# Quadrature_Mixers_FIXED_WITH_BIASING.net
KiCad netlist of a schematic drawn in Altium Designer
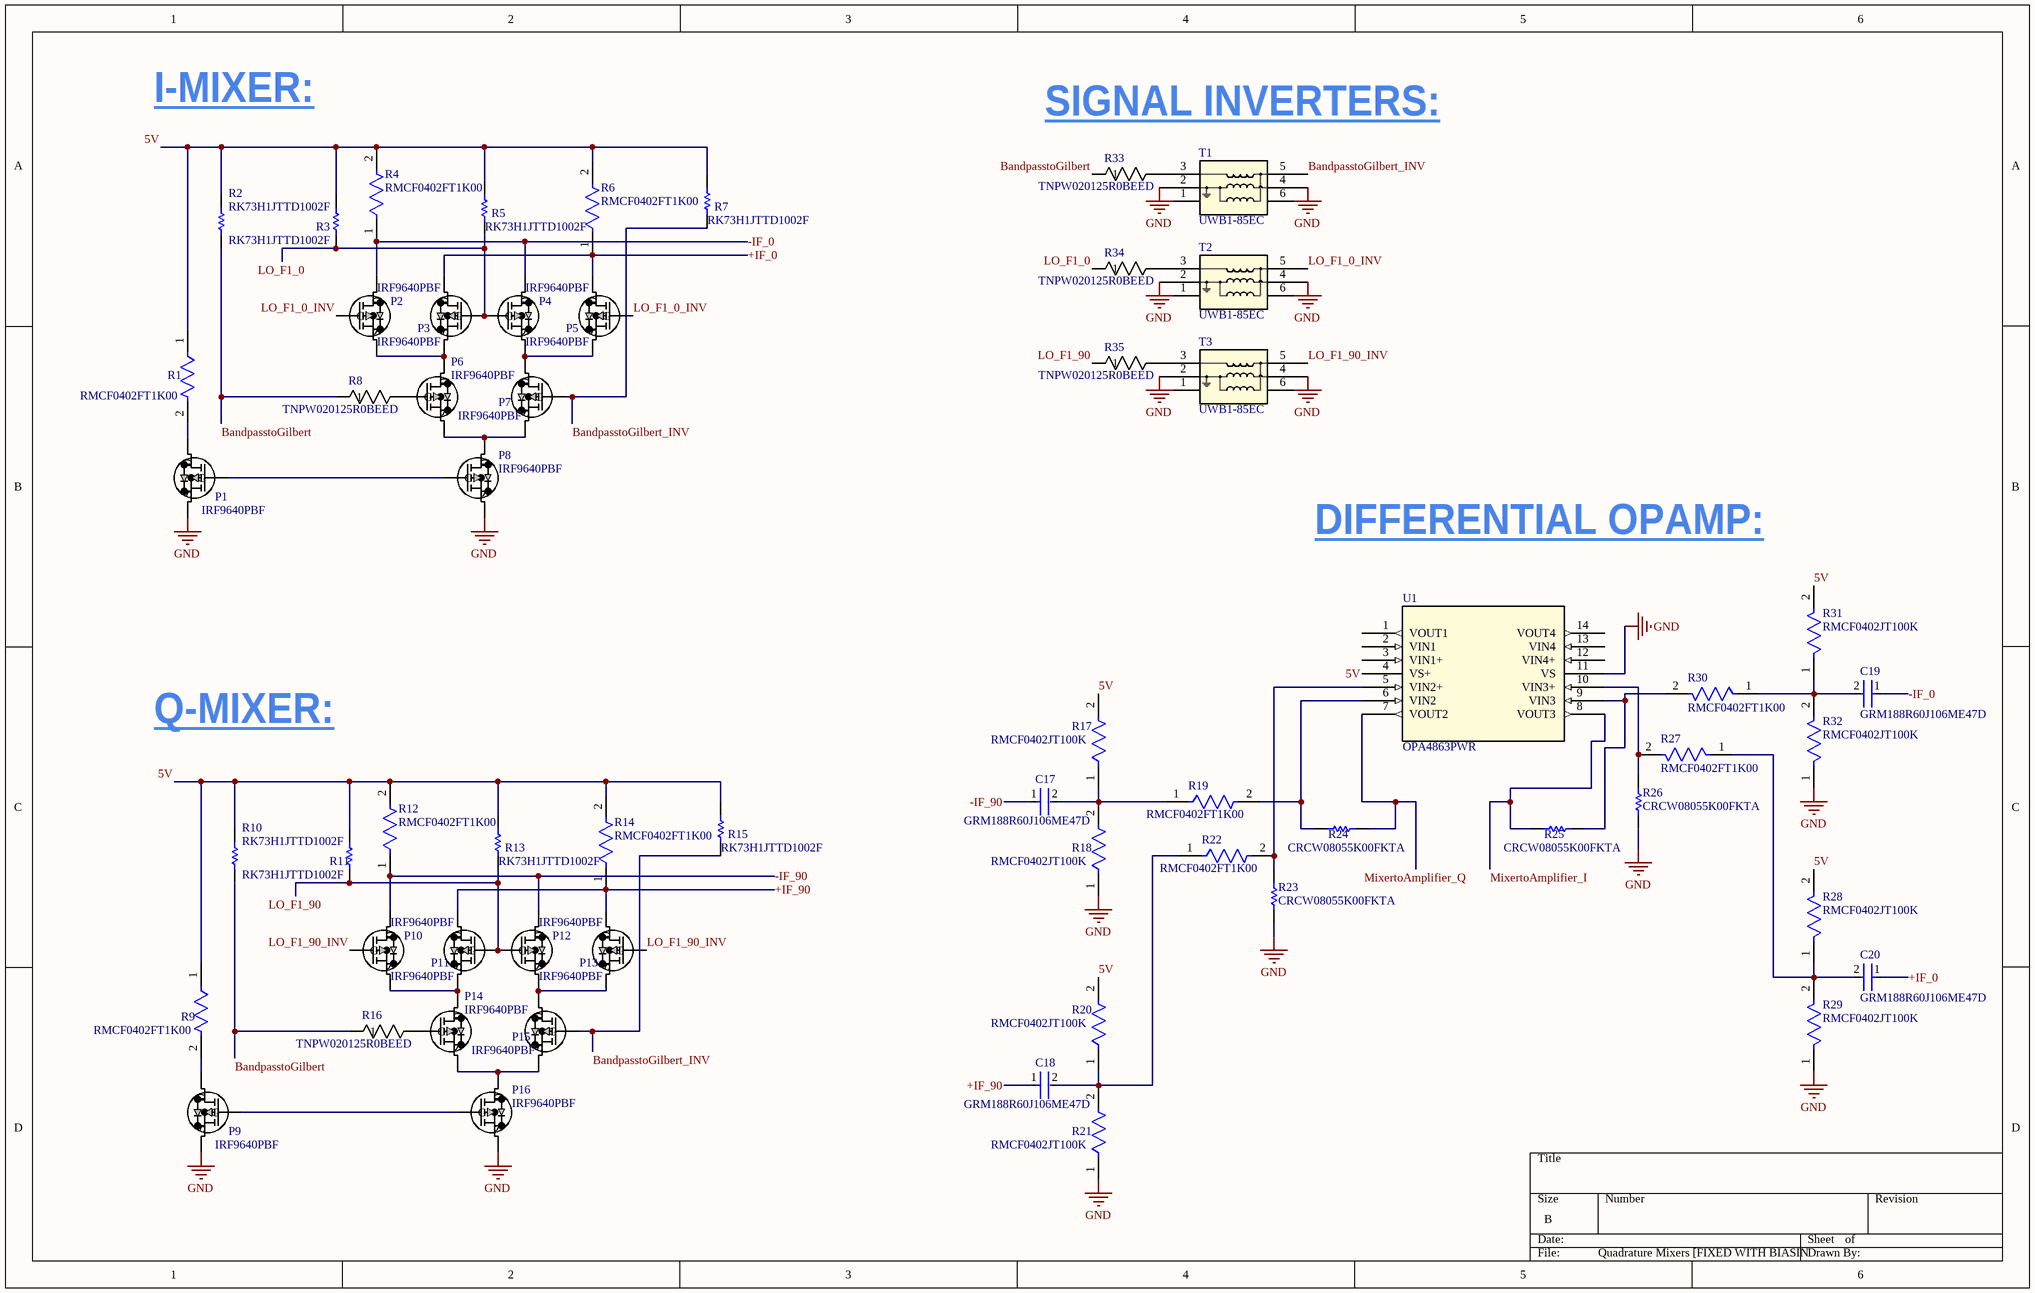
[diagram p0: Quadrature Mixers [FIXED WITH BIASING].SchDoc]

(export (version "E")
  (design (tool "Eeschema 10.0.6"))
  (components
    (comp (ref "C17")
      (value "GRM188R60J106ME47D")
      (footprint "FP-GRM188-0_1-e0_2_0_55-IPC_A")
      (description "Chip Multilayer Ceramic Capacitors for General Purpose, 0603, 10uF, X5R, 15%, 20%, 6.3V")
      (fields (field (name "VOLTAGE") "6.3V") (field (name "TOLERANCE") "20%"))
      (libsource (lib "Altium Content Vault") (part "02cd4be3c70576c341d710602a673aa"))
    )
    (comp (ref "C18")
      (value "GRM188R60J106ME47D")
      (footprint "FP-GRM188-0_1-e0_2_0_55-IPC_A")
      (description "Chip Multilayer Ceramic Capacitors for General Purpose, 0603, 10uF, X5R, 15%, 20%, 6.3V")
      (fields (field (name "VOLTAGE") "6.3V") (field (name "TOLERANCE") "20%"))
      (libsource (lib "Altium Content Vault") (part "02cd4be3c70576c341d710602a673aa"))
    )
    (comp (ref "C19")
      (value "GRM188R60J106ME47D")
      (footprint "FP-GRM188-0_1-e0_2_0_55-IPC_A")
      (description "Chip Multilayer Ceramic Capacitors for General Purpose, 0603, 10uF, X5R, 15%, 20%, 6.3V")
      (fields (field (name "VOLTAGE") "6.3V") (field (name "TOLERANCE") "20%"))
      (libsource (lib "Altium Content Vault") (part "02cd4be3c70576c341d710602a673aa"))
    )
    (comp (ref "C20")
      (value "GRM188R60J106ME47D")
      (footprint "FP-GRM188-0_1-e0_2_0_55-IPC_A")
      (description "Chip Multilayer Ceramic Capacitors for General Purpose, 0603, 10uF, X5R, 15%, 20%, 6.3V")
      (fields (field (name "VOLTAGE") "6.3V") (field (name "TOLERANCE") "20%"))
      (libsource (lib "Altium Content Vault") (part "02cd4be3c70576c341d710602a673aa"))
    )
    (comp (ref "P1")
      (value "IRF9640PBF")
      (footprint "TO220AB_VIS")
      (description "No Description Available")
      (libsource (lib "IRF9640PBF") (part "IRF9640PBF"))
    )
    (comp (ref "P2")
      (value "IRF9640PBF")
      (footprint "TO220AB_VIS")
      (description "No Description Available")
      (libsource (lib "IRF9640PBF") (part "IRF9640PBF"))
    )
    (comp (ref "P3")
      (value "IRF9640PBF")
      (footprint "TO220AB_VIS")
      (description "No Description Available")
      (libsource (lib "IRF9640PBF") (part "IRF9640PBF"))
    )
    (comp (ref "P4")
      (value "IRF9640PBF")
      (footprint "TO220AB_VIS")
      (description "No Description Available")
      (libsource (lib "IRF9640PBF") (part "IRF9640PBF"))
    )
    (comp (ref "P5")
      (value "IRF9640PBF")
      (footprint "TO220AB_VIS")
      (description "No Description Available")
      (libsource (lib "IRF9640PBF") (part "IRF9640PBF"))
    )
    (comp (ref "P6")
      (value "IRF9640PBF")
      (footprint "TO220AB_VIS")
      (description "No Description Available")
      (libsource (lib "IRF9640PBF") (part "IRF9640PBF"))
    )
    (comp (ref "P7")
      (value "IRF9640PBF")
      (footprint "TO220AB_VIS")
      (description "No Description Available")
      (libsource (lib "IRF9640PBF") (part "IRF9640PBF"))
    )
    (comp (ref "P8")
      (value "IRF9640PBF")
      (footprint "TO220AB_VIS")
      (description "No Description Available")
      (libsource (lib "IRF9640PBF") (part "IRF9640PBF"))
    )
    (comp (ref "P9")
      (value "IRF9640PBF")
      (footprint "TO220AB_VIS")
      (description "No Description Available")
      (libsource (lib "IRF9640PBF") (part "IRF9640PBF"))
    )
    (comp (ref "P10")
      (value "IRF9640PBF")
      (footprint "TO220AB_VIS")
      (description "No Description Available")
      (libsource (lib "IRF9640PBF") (part "IRF9640PBF"))
    )
    (comp (ref "P11")
      (value "IRF9640PBF")
      (footprint "TO220AB_VIS")
      (description "No Description Available")
      (libsource (lib "IRF9640PBF") (part "IRF9640PBF"))
    )
    (comp (ref "P12")
      (value "IRF9640PBF")
      (footprint "TO220AB_VIS")
      (description "No Description Available")
      (libsource (lib "IRF9640PBF") (part "IRF9640PBF"))
    )
    (comp (ref "P13")
      (value "IRF9640PBF")
      (footprint "TO220AB_VIS")
      (description "No Description Available")
      (libsource (lib "IRF9640PBF") (part "IRF9640PBF"))
    )
    (comp (ref "P14")
      (value "IRF9640PBF")
      (footprint "TO220AB_VIS")
      (description "No Description Available")
      (libsource (lib "IRF9640PBF") (part "IRF9640PBF"))
    )
    (comp (ref "P15")
      (value "IRF9640PBF")
      (footprint "TO220AB_VIS")
      (description "No Description Available")
      (libsource (lib "IRF9640PBF") (part "IRF9640PBF"))
    )
    (comp (ref "P16")
      (value "IRF9640PBF")
      (footprint "TO220AB_VIS")
      (description "No Description Available")
      (libsource (lib "IRF9640PBF") (part "IRF9640PBF"))
    )
    (comp (ref "R1")
      (value "RMCF0402FT1K00")
      (footprint "FP-RMCF0402-MFG")
      (description "1kΩ ±1% 0.063W 0402 Thick Film Chip Resistor AEC-Q200 compliant")
      (fields (field (name "TOLERANCE") "1%"))
      (libsource (lib "Altium Content Vault") (part "1029c3af85768c4190bb7ad29bc67b5"))
    )
    (comp (ref "R2")
      (value "RK73H1JTTD1002F")
      (footprint "RESC1608X55X30ML20T10")
      (fields (field (name "MANUFACTURER") "KOA Speer"))
      (libsource (lib "Altium Content Vault") (part "RES"))
    )
    (comp (ref "R3")
      (value "RK73H1JTTD1002F")
      (footprint "RESC1608X55X30ML20T10")
      (fields (field (name "MANUFACTURER") "KOA Speer"))
      (libsource (lib "Altium Content Vault") (part "RES"))
    )
    (comp (ref "R4")
      (value "RMCF0402FT1K00")
      (footprint "FP-RMCF0402-MFG")
      (description "1kΩ ±1% 0.063W 0402 Thick Film Chip Resistor AEC-Q200 compliant")
      (fields (field (name "TOLERANCE") "1%"))
      (libsource (lib "Altium Content Vault") (part "1029c3af85768c4190bb7ad29bc67b5"))
    )
    (comp (ref "R5")
      (value "RK73H1JTTD1002F")
      (footprint "RESC1608X55X30ML20T10")
      (fields (field (name "MANUFACTURER") "KOA Speer"))
      (libsource (lib "Altium Content Vault") (part "RES"))
    )
    (comp (ref "R6")
      (value "RMCF0402FT1K00")
      (footprint "FP-RMCF0402-MFG")
      (description "1kΩ ±1% 0.063W 0402 Thick Film Chip Resistor AEC-Q200 compliant")
      (fields (field (name "TOLERANCE") "1%"))
      (libsource (lib "Altium Content Vault") (part "1029c3af85768c4190bb7ad29bc67b5"))
    )
    (comp (ref "R7")
      (value "RK73H1JTTD1002F")
      (footprint "RESC1608X55X30ML20T10")
      (fields (field (name "MANUFACTURER") "KOA Speer"))
      (libsource (lib "Altium Content Vault") (part "RES"))
    )
    (comp (ref "R8")
      (value "TNPW020125R0BEED")
      (footprint "RES_TNPW0201_VIS")
      (description "RES 25 OHM 0.1% 0.075W 0201")
      (libsource (lib "TNPW020125R0BEED") (part "TNPW020125R0BEED"))
    )
    (comp (ref "R9")
      (value "RMCF0402FT1K00")
      (footprint "FP-RMCF0402-MFG")
      (description "1kΩ ±1% 0.063W 0402 Thick Film Chip Resistor AEC-Q200 compliant")
      (fields (field (name "TOLERANCE") "1%"))
      (libsource (lib "Altium Content Vault") (part "1029c3af85768c4190bb7ad29bc67b5"))
    )
    (comp (ref "R10")
      (value "RK73H1JTTD1002F")
      (footprint "RESC1608X55X30ML20T10")
      (fields (field (name "MANUFACTURER") "KOA Speer"))
      (libsource (lib "Altium Content Vault") (part "RES"))
    )
    (comp (ref "R11")
      (value "RK73H1JTTD1002F")
      (footprint "RESC1608X55X30ML20T10")
      (fields (field (name "MANUFACTURER") "KOA Speer"))
      (libsource (lib "Altium Content Vault") (part "RES"))
    )
    (comp (ref "R12")
      (value "RMCF0402FT1K00")
      (footprint "FP-RMCF0402-MFG")
      (description "1kΩ ±1% 0.063W 0402 Thick Film Chip Resistor AEC-Q200 compliant")
      (fields (field (name "TOLERANCE") "1%"))
      (libsource (lib "Altium Content Vault") (part "1029c3af85768c4190bb7ad29bc67b5"))
    )
    (comp (ref "R13")
      (value "RK73H1JTTD1002F")
      (footprint "RESC1608X55X30ML20T10")
      (fields (field (name "MANUFACTURER") "KOA Speer"))
      (libsource (lib "Altium Content Vault") (part "RES"))
    )
    (comp (ref "R14")
      (value "RMCF0402FT1K00")
      (footprint "FP-RMCF0402-MFG")
      (description "1kΩ ±1% 0.063W 0402 Thick Film Chip Resistor AEC-Q200 compliant")
      (fields (field (name "TOLERANCE") "1%"))
      (libsource (lib "Altium Content Vault") (part "1029c3af85768c4190bb7ad29bc67b5"))
    )
    (comp (ref "R15")
      (value "RK73H1JTTD1002F")
      (footprint "RESC1608X55X30ML20T10")
      (fields (field (name "MANUFACTURER") "KOA Speer"))
      (libsource (lib "Altium Content Vault") (part "RES"))
    )
    (comp (ref "R16")
      (value "TNPW020125R0BEED")
      (footprint "RES_TNPW0201_VIS")
      (description "RES 25 OHM 0.1% 0.075W 0201")
      (libsource (lib "TNPW020125R0BEED") (part "TNPW020125R0BEED"))
    )
    (comp (ref "R17")
      (value "RMCF0402JT100K")
      (footprint "FP-RMCF0402-MFG")
      (description "100kΩ ±5% 0.063W 0402 Thick Film Chip Resistor AEC-Q200 compliant")
      (fields (field (name "TOLERANCE") "5%"))
      (libsource (lib "Altium Content Vault") (part "1029c3af85768c4190bb7ad29bc67b5"))
    )
    (comp (ref "R18")
      (value "RMCF0402JT100K")
      (footprint "FP-RMCF0402-MFG")
      (description "100kΩ ±5% 0.063W 0402 Thick Film Chip Resistor AEC-Q200 compliant")
      (fields (field (name "TOLERANCE") "5%"))
      (libsource (lib "Altium Content Vault") (part "1029c3af85768c4190bb7ad29bc67b5"))
    )
    (comp (ref "R19")
      (value "RMCF0402FT1K00")
      (footprint "FP-RMCF0402-MFG")
      (description "1kΩ ±1% 0.063W 0402 Thick Film Chip Resistor AEC-Q200 compliant")
      (fields (field (name "TOLERANCE") "1%"))
      (libsource (lib "Altium Content Vault") (part "1029c3af85768c4190bb7ad29bc67b5"))
    )
    (comp (ref "R20")
      (value "RMCF0402JT100K")
      (footprint "FP-RMCF0402-MFG")
      (description "100kΩ ±5% 0.063W 0402 Thick Film Chip Resistor AEC-Q200 compliant")
      (fields (field (name "TOLERANCE") "5%"))
      (libsource (lib "Altium Content Vault") (part "1029c3af85768c4190bb7ad29bc67b5"))
    )
    (comp (ref "R21")
      (value "RMCF0402JT100K")
      (footprint "FP-RMCF0402-MFG")
      (description "100kΩ ±5% 0.063W 0402 Thick Film Chip Resistor AEC-Q200 compliant")
      (fields (field (name "TOLERANCE") "5%"))
      (libsource (lib "Altium Content Vault") (part "1029c3af85768c4190bb7ad29bc67b5"))
    )
    (comp (ref "R22")
      (value "RMCF0402FT1K00")
      (footprint "FP-RMCF0402-MFG")
      (description "1kΩ ±1% 0.063W 0402 Thick Film Chip Resistor AEC-Q200 compliant")
      (fields (field (name "TOLERANCE") "1%"))
      (libsource (lib "Altium Content Vault") (part "1029c3af85768c4190bb7ad29bc67b5"))
    )
    (comp (ref "R23")
      (value "CRCW08055K00FKTA")
      (footprint "RESC2013X50X30ML20T20")
      (fields (field (name "MANUFACTURER") "Vishay Dale"))
      (libsource (lib "Altium Content Vault") (part "RES"))
    )
    (comp (ref "R24")
      (value "CRCW08055K00FKTA")
      (footprint "RESC2013X50X30ML20T20")
      (fields (field (name "MANUFACTURER") "Vishay Dale"))
      (libsource (lib "Altium Content Vault") (part "RES"))
    )
    (comp (ref "R25")
      (value "CRCW08055K00FKTA")
      (footprint "RESC2013X50X30ML20T20")
      (fields (field (name "MANUFACTURER") "Vishay Dale"))
      (libsource (lib "Altium Content Vault") (part "RES"))
    )
    (comp (ref "R26")
      (value "CRCW08055K00FKTA")
      (footprint "RESC2013X50X30ML20T20")
      (fields (field (name "MANUFACTURER") "Vishay Dale"))
      (libsource (lib "Altium Content Vault") (part "RES"))
    )
    (comp (ref "R27")
      (value "RMCF0402FT1K00")
      (footprint "FP-RMCF0402-MFG")
      (description "1kΩ ±1% 0.063W 0402 Thick Film Chip Resistor AEC-Q200 compliant")
      (fields (field (name "TOLERANCE") "1%"))
      (libsource (lib "Altium Content Vault") (part "1029c3af85768c4190bb7ad29bc67b5"))
    )
    (comp (ref "R28")
      (value "RMCF0402JT100K")
      (footprint "FP-RMCF0402-MFG")
      (description "100kΩ ±5% 0.063W 0402 Thick Film Chip Resistor AEC-Q200 compliant")
      (fields (field (name "TOLERANCE") "5%"))
      (libsource (lib "Altium Content Vault") (part "1029c3af85768c4190bb7ad29bc67b5"))
    )
    (comp (ref "R29")
      (value "RMCF0402JT100K")
      (footprint "FP-RMCF0402-MFG")
      (description "100kΩ ±5% 0.063W 0402 Thick Film Chip Resistor AEC-Q200 compliant")
      (fields (field (name "TOLERANCE") "5%"))
      (libsource (lib "Altium Content Vault") (part "1029c3af85768c4190bb7ad29bc67b5"))
    )
    (comp (ref "R30")
      (value "RMCF0402FT1K00")
      (footprint "FP-RMCF0402-MFG")
      (description "1kΩ ±1% 0.063W 0402 Thick Film Chip Resistor AEC-Q200 compliant")
      (fields (field (name "TOLERANCE") "1%"))
      (libsource (lib "Altium Content Vault") (part "1029c3af85768c4190bb7ad29bc67b5"))
    )
    (comp (ref "R31")
      (value "RMCF0402JT100K")
      (footprint "FP-RMCF0402-MFG")
      (description "100kΩ ±5% 0.063W 0402 Thick Film Chip Resistor AEC-Q200 compliant")
      (fields (field (name "TOLERANCE") "5%"))
      (libsource (lib "Altium Content Vault") (part "1029c3af85768c4190bb7ad29bc67b5"))
    )
    (comp (ref "R32")
      (value "RMCF0402JT100K")
      (footprint "FP-RMCF0402-MFG")
      (description "100kΩ ±5% 0.063W 0402 Thick Film Chip Resistor AEC-Q200 compliant")
      (fields (field (name "TOLERANCE") "5%"))
      (libsource (lib "Altium Content Vault") (part "1029c3af85768c4190bb7ad29bc67b5"))
    )
    (comp (ref "R33")
      (value "TNPW020125R0BEED")
      (footprint "RES_TNPW0201_VIS")
      (description "RES 25 OHM 0.1% 0.075W 0201")
      (libsource (lib "TNPW020125R0BEED") (part "TNPW020125R0BEED"))
    )
    (comp (ref "R34")
      (value "TNPW020125R0BEED")
      (footprint "RES_TNPW0201_VIS")
      (description "RES 25 OHM 0.1% 0.075W 0201")
      (libsource (lib "TNPW020125R0BEED") (part "TNPW020125R0BEED"))
    )
    (comp (ref "R35")
      (value "TNPW020125R0BEED")
      (footprint "RES_TNPW0201_VIS")
      (description "RES 25 OHM 0.1% 0.075W 0201")
      (libsource (lib "TNPW020125R0BEED") (part "TNPW020125R0BEED"))
    )
    (comp (ref "T1")
      (value "UWB1-85EC")
      (footprint "UWB1UWB2_COC")
      (libsource (lib "UWB1-85EC") (part "UWB1-85EC"))
    )
    (comp (ref "T2")
      (value "UWB1-85EC")
      (footprint "UWB1UWB2_COC")
      (libsource (lib "UWB1-85EC") (part "UWB1-85EC"))
    )
    (comp (ref "T3")
      (value "UWB1-85EC")
      (footprint "UWB1UWB2_COC")
      (libsource (lib "UWB1-85EC") (part "UWB1-85EC"))
    )
    (comp (ref "U1")
      (value "OPA4863PWR")
      (footprint "PW14_TEX")
      (description "No Description Available")
      (libsource (lib "OPA4863PWR") (part "OPA4863PWR"))
    )
  )
  (nets
    (net (code "1") (name "/+IF_0") (class "Default")
      (node (ref "C20") (pin "1") (pinfunction "1_1") (pintype "passive"))
      (node (ref "P3") (pin "2") (pinfunction "D_2") (pintype "passive"))
      (node (ref "P5") (pin "2") (pinfunction "D_2") (pintype "passive"))
      (node (ref "R6") (pin "1") (pinfunction "1_1") (pintype "passive"))
    )
    (net (code "2") (name "/+IF_90") (class "Default")
      (node (ref "C18") (pin "1") (pinfunction "1_1") (pintype "passive"))
      (node (ref "P11") (pin "2") (pinfunction "D_2") (pintype "passive"))
      (node (ref "P13") (pin "2") (pinfunction "D_2") (pintype "passive"))
      (node (ref "R14") (pin "1") (pinfunction "1_1") (pintype "passive"))
    )
    (net (code "3") (name "/-IF_0") (class "Default")
      (node (ref "C19") (pin "1") (pinfunction "1_1") (pintype "passive"))
      (node (ref "P2") (pin "2") (pinfunction "D_2") (pintype "passive"))
      (node (ref "P4") (pin "2") (pinfunction "D_2") (pintype "passive"))
      (node (ref "R4") (pin "1") (pinfunction "1_1") (pintype "passive"))
    )
    (net (code "4") (name "/-IF_90") (class "Default")
      (node (ref "C17") (pin "1") (pinfunction "1_1") (pintype "passive"))
      (node (ref "P10") (pin "2") (pinfunction "D_2") (pintype "passive"))
      (node (ref "P12") (pin "2") (pinfunction "D_2") (pintype "passive"))
      (node (ref "R12") (pin "1") (pinfunction "1_1") (pintype "passive"))
    )
    (net (code "5") (name "/5V") (class "Default")
      (node (ref "R1") (pin "1") (pinfunction "1_1") (pintype "passive"))
      (node (ref "R10") (pin "2") (pinfunction "2_2") (pintype "passive"))
      (node (ref "R11") (pin "2") (pinfunction "2_2") (pintype "passive"))
      (node (ref "R12") (pin "2") (pinfunction "2_2") (pintype "passive"))
      (node (ref "R13") (pin "2") (pinfunction "2_2") (pintype "passive"))
      (node (ref "R14") (pin "2") (pinfunction "2_2") (pintype "passive"))
      (node (ref "R15") (pin "2") (pinfunction "2_2") (pintype "passive"))
      (node (ref "R17") (pin "2") (pinfunction "2_2") (pintype "passive"))
      (node (ref "R2") (pin "2") (pinfunction "2_2") (pintype "passive"))
      (node (ref "R20") (pin "2") (pinfunction "2_2") (pintype "passive"))
      (node (ref "R28") (pin "2") (pinfunction "2_2") (pintype "passive"))
      (node (ref "R3") (pin "2") (pinfunction "2_2") (pintype "passive"))
      (node (ref "R31") (pin "2") (pinfunction "2_2") (pintype "passive"))
      (node (ref "R4") (pin "2") (pinfunction "2_2") (pintype "passive"))
      (node (ref "R5") (pin "2") (pinfunction "2_2") (pintype "passive"))
      (node (ref "R6") (pin "2") (pinfunction "2_2") (pintype "passive"))
      (node (ref "R7") (pin "2") (pinfunction "2_2") (pintype "passive"))
      (node (ref "R9") (pin "1") (pinfunction "1_1") (pintype "passive"))
      (node (ref "U1") (pin "4") (pinfunction "VS+_4") (pintype "power_in"))
    )
    (net (code "6") (name "/BandpasstoGilbert") (class "Default")
      (node (ref "R10") (pin "1") (pinfunction "1_1") (pintype "passive"))
      (node (ref "R16") (pin "1") (pinfunction "1_1") (pintype "passive"))
      (node (ref "R2") (pin "1") (pinfunction "1_1") (pintype "passive"))
      (node (ref "R33") (pin "1") (pinfunction "1_1") (pintype "passive"))
      (node (ref "R8") (pin "1") (pinfunction "1_1") (pintype "passive"))
    )
    (net (code "7") (name "/BandpasstoGilbert_INV") (class "Default")
      (node (ref "P15") (pin "1") (pinfunction "G_1") (pintype "passive"))
      (node (ref "P7") (pin "1") (pinfunction "G_1") (pintype "passive"))
      (node (ref "R15") (pin "1") (pinfunction "1_1") (pintype "passive"))
      (node (ref "R7") (pin "1") (pinfunction "1_1") (pintype "passive"))
      (node (ref "T1") (pin "5") (pinfunction "5_5") (pintype "passive"))
    )
    (net (code "8") (name "/LO_F1_0") (class "Default")
      (node (ref "P3") (pin "1") (pinfunction "G_1") (pintype "passive"))
      (node (ref "P4") (pin "1") (pinfunction "G_1") (pintype "passive"))
      (node (ref "R3") (pin "1") (pinfunction "1_1") (pintype "passive"))
      (node (ref "R34") (pin "1") (pinfunction "1_1") (pintype "passive"))
      (node (ref "R5") (pin "1") (pinfunction "1_1") (pintype "passive"))
    )
    (net (code "9") (name "/LO_F1_0_INV") (class "Default")
      (node (ref "P2") (pin "1") (pinfunction "G_1") (pintype "passive"))
      (node (ref "P5") (pin "1") (pinfunction "G_1") (pintype "passive"))
      (node (ref "T2") (pin "5") (pinfunction "5_5") (pintype "passive"))
    )
    (net (code "10") (name "/LO_F1_90") (class "Default")
      (node (ref "P11") (pin "1") (pinfunction "G_1") (pintype "passive"))
      (node (ref "P12") (pin "1") (pinfunction "G_1") (pintype "passive"))
      (node (ref "R11") (pin "1") (pinfunction "1_1") (pintype "passive"))
      (node (ref "R13") (pin "1") (pinfunction "1_1") (pintype "passive"))
      (node (ref "R35") (pin "1") (pinfunction "1_1") (pintype "passive"))
    )
    (net (code "11") (name "/LO_F1_90_INV") (class "Default")
      (node (ref "P10") (pin "1") (pinfunction "G_1") (pintype "passive"))
      (node (ref "P13") (pin "1") (pinfunction "G_1") (pintype "passive"))
      (node (ref "T3") (pin "5") (pinfunction "5_5") (pintype "passive"))
    )
    (net (code "12") (name "/MixertoAmplifier_I") (class "Default")
      (node (ref "R25") (pin "1") (pinfunction "1_1") (pintype "passive"))
      (node (ref "U1") (pin "8") (pinfunction "VOUT3_8") (pintype "output"))
    )
    (net (code "13") (name "/MixertoAmplifier_Q") (class "Default")
      (node (ref "R24") (pin "2") (pinfunction "2_2") (pintype "passive"))
      (node (ref "U1") (pin "7") (pinfunction "VOUT2_7") (pintype "output"))
    )
    (net (code "14") (name "GND") (class "Default")
      (node (ref "P1") (pin "3") (pinfunction "S_3") (pintype "passive"))
      (node (ref "P16") (pin "3") (pinfunction "S_3") (pintype "passive"))
      (node (ref "P8") (pin "3") (pinfunction "S_3") (pintype "passive"))
      (node (ref "P9") (pin "3") (pinfunction "S_3") (pintype "passive"))
      (node (ref "R18") (pin "1") (pinfunction "1_1") (pintype "passive"))
      (node (ref "R21") (pin "1") (pinfunction "1_1") (pintype "passive"))
      (node (ref "R23") (pin "1") (pinfunction "1_1") (pintype "passive"))
      (node (ref "R26") (pin "1") (pinfunction "1_1") (pintype "passive"))
      (node (ref "R29") (pin "1") (pinfunction "1_1") (pintype "passive"))
      (node (ref "R32") (pin "1") (pinfunction "1_1") (pintype "passive"))
      (node (ref "T1") (pin "2") (pinfunction "2_2") (pintype "passive"))
      (node (ref "T1") (pin "4") (pinfunction "4_4") (pintype "passive"))
      (node (ref "T2") (pin "2") (pinfunction "2_2") (pintype "passive"))
      (node (ref "T2") (pin "4") (pinfunction "4_4") (pintype "passive"))
      (node (ref "T3") (pin "2") (pinfunction "2_2") (pintype "passive"))
      (node (ref "T3") (pin "4") (pinfunction "4_4") (pintype "passive"))
      (node (ref "U1") (pin "11") (pinfunction "VS_11") (pintype "power_in"))
    )
    (net (code "15") (name "Net-(C17-Pad2)") (class "Default")
      (node (ref "C17") (pin "2") (pinfunction "2_2") (pintype "passive"))
      (node (ref "R17") (pin "1") (pinfunction "1_1") (pintype "passive"))
      (node (ref "R18") (pin "2") (pinfunction "2_2") (pintype "passive"))
      (node (ref "R19") (pin "1") (pinfunction "1_1") (pintype "passive"))
    )
    (net (code "16") (name "Net-(C18-Pad2)") (class "Default")
      (node (ref "C18") (pin "2") (pinfunction "2_2") (pintype "passive"))
      (node (ref "R20") (pin "1") (pinfunction "1_1") (pintype "passive"))
      (node (ref "R21") (pin "2") (pinfunction "2_2") (pintype "passive"))
      (node (ref "R22") (pin "1") (pinfunction "1_1") (pintype "passive"))
    )
    (net (code "17") (name "Net-(C19-Pad2)") (class "Default")
      (node (ref "C19") (pin "2") (pinfunction "2_2") (pintype "passive"))
      (node (ref "R30") (pin "1") (pinfunction "1_1") (pintype "passive"))
      (node (ref "R31") (pin "1") (pinfunction "1_1") (pintype "passive"))
      (node (ref "R32") (pin "2") (pinfunction "2_2") (pintype "passive"))
    )
    (net (code "18") (name "Net-(C20-Pad2)") (class "Default")
      (node (ref "C20") (pin "2") (pinfunction "2_2") (pintype "passive"))
      (node (ref "R27") (pin "1") (pinfunction "1_1") (pintype "passive"))
      (node (ref "R28") (pin "1") (pinfunction "1_1") (pintype "passive"))
      (node (ref "R29") (pin "2") (pinfunction "2_2") (pintype "passive"))
    )
    (net (code "19") (name "Net-(P1-D)") (class "Default")
      (node (ref "P1") (pin "2") (pinfunction "D_2") (pintype "passive"))
      (node (ref "R1") (pin "2") (pinfunction "2_2") (pintype "passive"))
    )
    (net (code "20") (name "Net-(P1-G)") (class "Default")
      (node (ref "P1") (pin "1") (pinfunction "G_1") (pintype "passive"))
      (node (ref "P8") (pin "1") (pinfunction "G_1") (pintype "passive"))
    )
    (net (code "21") (name "Net-(P2-S)") (class "Default")
      (node (ref "P2") (pin "3") (pinfunction "S_3") (pintype "passive"))
      (node (ref "P3") (pin "3") (pinfunction "S_3") (pintype "passive"))
      (node (ref "P6") (pin "2") (pinfunction "D_2") (pintype "passive"))
    )
    (net (code "22") (name "Net-(P4-S)") (class "Default")
      (node (ref "P4") (pin "3") (pinfunction "S_3") (pintype "passive"))
      (node (ref "P5") (pin "3") (pinfunction "S_3") (pintype "passive"))
      (node (ref "P7") (pin "2") (pinfunction "D_2") (pintype "passive"))
    )
    (net (code "23") (name "Net-(P6-G)") (class "Default")
      (node (ref "P6") (pin "1") (pinfunction "G_1") (pintype "passive"))
      (node (ref "R8") (pin "2") (pinfunction "2_2") (pintype "passive"))
    )
    (net (code "24") (name "Net-(P6-S)") (class "Default")
      (node (ref "P6") (pin "3") (pinfunction "S_3") (pintype "passive"))
      (node (ref "P7") (pin "3") (pinfunction "S_3") (pintype "passive"))
      (node (ref "P8") (pin "2") (pinfunction "D_2") (pintype "passive"))
    )
    (net (code "25") (name "Net-(P9-D)") (class "Default")
      (node (ref "P9") (pin "2") (pinfunction "D_2") (pintype "passive"))
      (node (ref "R9") (pin "2") (pinfunction "2_2") (pintype "passive"))
    )
    (net (code "26") (name "Net-(P10-S)") (class "Default")
      (node (ref "P10") (pin "3") (pinfunction "S_3") (pintype "passive"))
      (node (ref "P11") (pin "3") (pinfunction "S_3") (pintype "passive"))
      (node (ref "P14") (pin "2") (pinfunction "D_2") (pintype "passive"))
    )
    (net (code "27") (name "Net-(P12-S)") (class "Default")
      (node (ref "P12") (pin "3") (pinfunction "S_3") (pintype "passive"))
      (node (ref "P13") (pin "3") (pinfunction "S_3") (pintype "passive"))
      (node (ref "P15") (pin "2") (pinfunction "D_2") (pintype "passive"))
    )
    (net (code "28") (name "Net-(P14-G)") (class "Default")
      (node (ref "P14") (pin "1") (pinfunction "G_1") (pintype "passive"))
      (node (ref "R16") (pin "2") (pinfunction "2_2") (pintype "passive"))
    )
    (net (code "29") (name "Net-(P14-S)") (class "Default")
      (node (ref "P14") (pin "3") (pinfunction "S_3") (pintype "passive"))
      (node (ref "P15") (pin "3") (pinfunction "S_3") (pintype "passive"))
      (node (ref "P16") (pin "2") (pinfunction "D_2") (pintype "passive"))
    )
    (net (code "30") (name "Net-(P16-G)") (class "Default")
      (node (ref "P16") (pin "1") (pinfunction "G_1") (pintype "passive"))
      (node (ref "P9") (pin "1") (pinfunction "G_1") (pintype "passive"))
    )
    (net (code "31") (name "Net-(R33-Pad2)") (class "Default")
      (node (ref "R33") (pin "2") (pinfunction "2_2") (pintype "passive"))
      (node (ref "T1") (pin "3") (pinfunction "3_3") (pintype "passive"))
    )
    (net (code "32") (name "Net-(R34-Pad2)") (class "Default")
      (node (ref "R34") (pin "2") (pinfunction "2_2") (pintype "passive"))
      (node (ref "T2") (pin "3") (pinfunction "3_3") (pintype "passive"))
    )
    (net (code "33") (name "Net-(R35-Pad2)") (class "Default")
      (node (ref "R35") (pin "2") (pinfunction "2_2") (pintype "passive"))
      (node (ref "T3") (pin "3") (pinfunction "3_3") (pintype "passive"))
    )
    (net (code "34") (name "Net-(U1-VIN2)") (class "Default")
      (node (ref "R19") (pin "2") (pinfunction "2_2") (pintype "passive"))
      (node (ref "R24") (pin "1") (pinfunction "1_1") (pintype "passive"))
      (node (ref "U1") (pin "6") (pinfunction "VIN2_6") (pintype "input"))
    )
    (net (code "35") (name "Net-(U1-VIN2+)") (class "Default")
      (node (ref "R22") (pin "2") (pinfunction "2_2") (pintype "passive"))
      (node (ref "R23") (pin "2") (pinfunction "2_2") (pintype "passive"))
      (node (ref "U1") (pin "5") (pinfunction "VIN2+_5") (pintype "input"))
    )
    (net (code "36") (name "Net-(U1-VIN3)") (class "Default")
      (node (ref "R25") (pin "2") (pinfunction "2_2") (pintype "passive"))
      (node (ref "R30") (pin "2") (pinfunction "2_2") (pintype "passive"))
      (node (ref "U1") (pin "9") (pinfunction "VIN3_9") (pintype "input"))
    )
    (net (code "37") (name "Net-(U1-VIN3+)") (class "Default")
      (node (ref "R26") (pin "2") (pinfunction "2_2") (pintype "passive"))
      (node (ref "R27") (pin "2") (pinfunction "2_2") (pintype "passive"))
      (node (ref "U1") (pin "10") (pinfunction "VIN3+_10") (pintype "input"))
    )
    (net (code "38") (name "unconnected-(T1-Pad1)") (class "Default")
      (node (ref "T1") (pin "1") (pinfunction "1_1") (pintype "passive"))
    )
    (net (code "39") (name "unconnected-(T1-Pad6)") (class "Default")
      (node (ref "T1") (pin "6") (pinfunction "6_6") (pintype "passive"))
    )
    (net (code "40") (name "unconnected-(T2-Pad1)") (class "Default")
      (node (ref "T2") (pin "1") (pinfunction "1_1") (pintype "passive"))
    )
    (net (code "41") (name "unconnected-(T2-Pad6)") (class "Default")
      (node (ref "T2") (pin "6") (pinfunction "6_6") (pintype "passive"))
    )
    (net (code "42") (name "unconnected-(T3-Pad1)") (class "Default")
      (node (ref "T3") (pin "1") (pinfunction "1_1") (pintype "passive"))
    )
    (net (code "43") (name "unconnected-(T3-Pad6)") (class "Default")
      (node (ref "T3") (pin "6") (pinfunction "6_6") (pintype "passive"))
    )
    (net (code "44") (name "unconnected-(U1-VIN1+-Pad3)") (class "Default")
      (node (ref "U1") (pin "3") (pinfunction "VIN1+_3") (pintype "input"))
    )
    (net (code "45") (name "unconnected-(U1-VIN1-Pad2)") (class "Default")
      (node (ref "U1") (pin "2") (pinfunction "VIN1_2") (pintype "input"))
    )
    (net (code "46") (name "unconnected-(U1-VIN4+-Pad12)") (class "Default")
      (node (ref "U1") (pin "12") (pinfunction "VIN4+_12") (pintype "input"))
    )
    (net (code "47") (name "unconnected-(U1-VIN4-Pad13)") (class "Default")
      (node (ref "U1") (pin "13") (pinfunction "VIN4_13") (pintype "input"))
    )
    (net (code "48") (name "unconnected-(U1-VOUT1-Pad1)") (class "Default")
      (node (ref "U1") (pin "1") (pinfunction "VOUT1_1") (pintype "output"))
    )
    (net (code "49") (name "unconnected-(U1-VOUT4-Pad14)") (class "Default")
      (node (ref "U1") (pin "14") (pinfunction "VOUT4_14") (pintype "output"))
    )
  )
)
